# CPU.net
KiCad netlist of a schematic drawn in Altium Designer
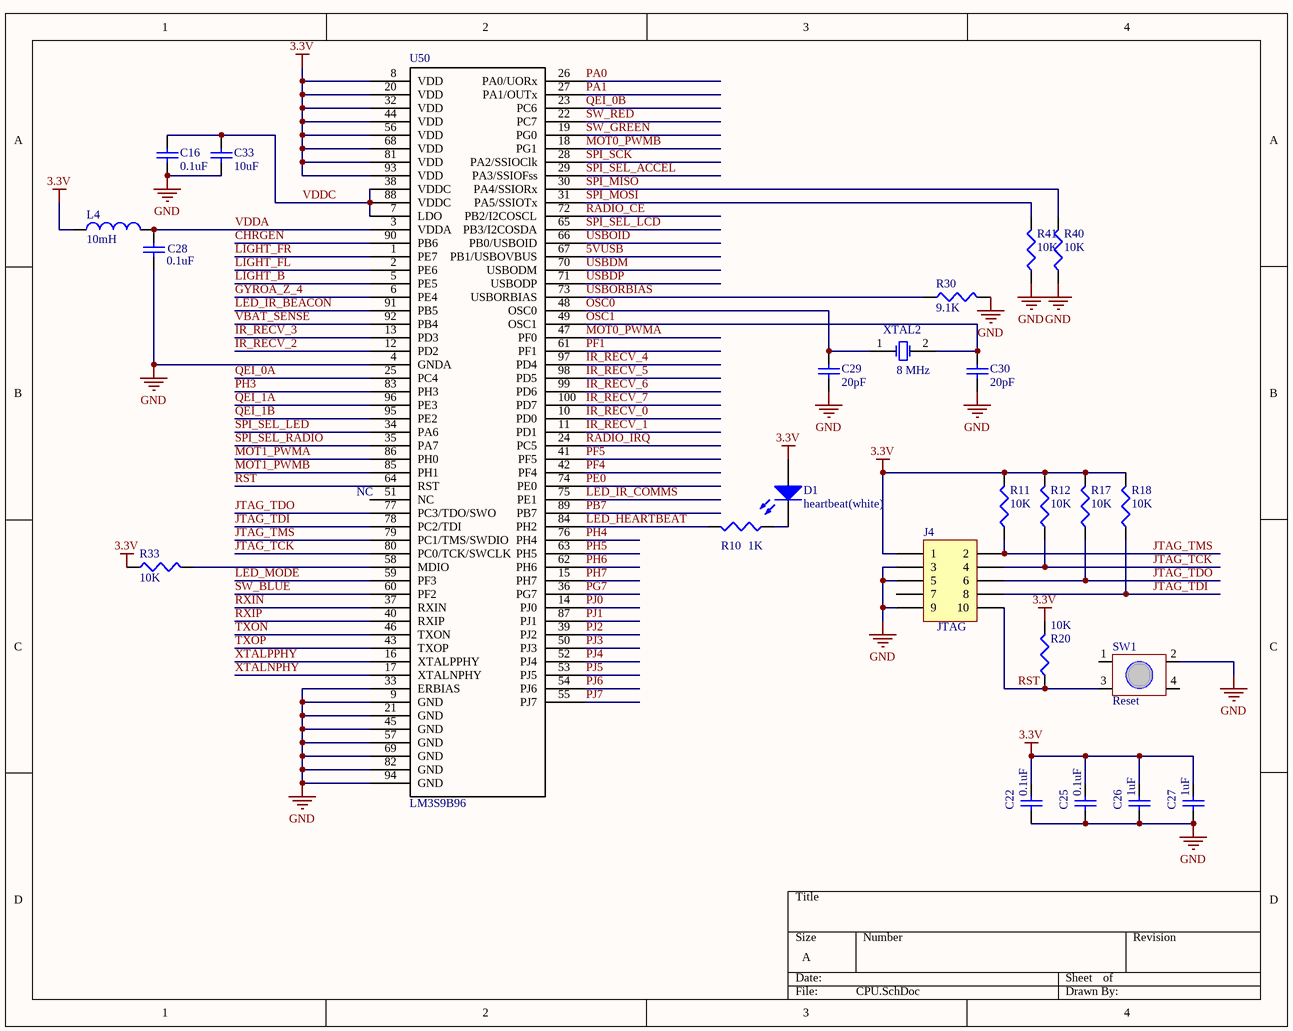
[diagram p0: CPU.SchDoc]

(export (version "E")
  (design (tool "Eeschema 10.0.6"))
  (components
    (comp (ref "C16")
      (value "0.1uF")
      (footprint "CAPC1005L")
      (description "Capacitor (Semiconductor SIM Model)")
      (fields (field (name "Comment") "Cap Semi") (field (name "PUBLISHER") "Altium Limited"))
      (libsource (lib "Miscellaneous Devices") (part "Cap Semi"))
    )
    (comp (ref "C22")
      (value "0.1uF")
      (footprint "CAPC1005L")
      (description "Capacitor (Semiconductor SIM Model)")
      (fields (field (name "Comment") "Cap Semi") (field (name "PUBLISHER") "Altium Limited"))
      (libsource (lib "Miscellaneous Devices") (part "Cap Semi"))
    )
    (comp (ref "C25")
      (value "0.1uF")
      (footprint "CAPC1005L")
      (description "Capacitor (Semiconductor SIM Model)")
      (fields (field (name "Comment") "Cap Semi") (field (name "PUBLISHER") "Altium Limited"))
      (libsource (lib "Miscellaneous Devices") (part "Cap Semi"))
    )
    (comp (ref "C26")
      (value "1uF")
      (footprint "CAPC1608L")
      (description "Capacitor (Semiconductor SIM Model)")
      (fields (field (name "Comment") "Cap Semi") (field (name "PUBLISHER") "Altium Limited"))
      (libsource (lib "Miscellaneous Devices") (part "Cap Semi"))
    )
    (comp (ref "C27")
      (value "1uF")
      (footprint "CAPC1608L")
      (description "Capacitor (Semiconductor SIM Model)")
      (fields (field (name "Comment") "Cap Semi") (field (name "PUBLISHER") "Altium Limited"))
      (libsource (lib "Miscellaneous Devices") (part "Cap Semi"))
    )
    (comp (ref "C28")
      (value "0.1uF")
      (footprint "CAPC1005L")
      (description "Capacitor (Semiconductor SIM Model)")
      (fields (field (name "Comment") "Cap Semi") (field (name "PUBLISHER") "Altium Limited"))
      (libsource (lib "Miscellaneous Devices") (part "Cap Semi"))
    )
    (comp (ref "C29")
      (value "20pF")
      (footprint "CAPC1005L")
      (description "Capacitor (Semiconductor SIM Model)")
      (fields (field (name "Comment") "Cap Semi") (field (name "PUBLISHER") "Altium Limited"))
      (libsource (lib "Miscellaneous Devices") (part "Cap Semi"))
    )
    (comp (ref "C30")
      (value "20pF")
      (footprint "CAPC1005L")
      (description "Capacitor (Semiconductor SIM Model)")
      (fields (field (name "Comment") "Cap Semi") (field (name "PUBLISHER") "Altium Limited"))
      (libsource (lib "Miscellaneous Devices") (part "Cap Semi"))
    )
    (comp (ref "C33")
      (value "10uF")
      (footprint "CAPC1005L")
      (description "Capacitor (Semiconductor SIM Model)")
      (fields (field (name "Comment") "Cap Semi") (field (name "PUBLISHER") "Altium Limited"))
      (libsource (lib "Miscellaneous Devices") (part "Cap Semi"))
    )
    (comp (ref "D1")
      (value "heartbeat(white)")
      (footprint "INDC2012L")
      (description "Typical RED, GREEN, YELLOW, AMBER GaAs LED")
      (fields (field (name "PUBLISHER") "Altium Limited"))
      (libsource (lib "Miscellaneous Devices") (part "LED2"))
    )
    (comp (ref "J4")
      (value "JTAG")
      (footprint "JTAG-10")
      (description "Header, 5-Pin, Dual row, Right Angle")
      (fields (field (name "PUBLISHER") "Altium Limited"))
      (libsource (lib "Miscellaneous Connectors") (part "Header 5X2H"))
    )
    (comp (ref "L4")
      (value "10mH")
      (footprint "INDC2012L")
      (description "Inductor")
      (fields (field (name "PUBLISHER") "Altium Limited"))
      (libsource (lib "Miscellaneous Devices") (part "Inductor"))
    )
    (comp (ref "R10")
      (value "1K")
      (footprint "RESC1608L")
      (description "Resistor")
      (fields (field (name "Comment") "Res3") (field (name "PUBLISHER") "Altium Limited"))
      (libsource (lib "Miscellaneous Devices") (part "Res3"))
    )
    (comp (ref "R11")
      (value "10K")
      (footprint "RESC1608L")
      (description "Resistor")
      (fields (field (name "Comment") "Res3") (field (name "PUBLISHER") "Altium Limited"))
      (libsource (lib "Miscellaneous Devices") (part "Res3"))
    )
    (comp (ref "R12")
      (value "10K")
      (footprint "RESC1608L")
      (description "Resistor")
      (fields (field (name "Comment") "Res3") (field (name "PUBLISHER") "Altium Limited"))
      (libsource (lib "Miscellaneous Devices") (part "Res3"))
    )
    (comp (ref "R17")
      (value "10K")
      (footprint "RESC1608L")
      (description "Resistor")
      (fields (field (name "Comment") "Res3") (field (name "PUBLISHER") "Altium Limited"))
      (libsource (lib "Miscellaneous Devices") (part "Res3"))
    )
    (comp (ref "R18")
      (value "10K")
      (footprint "RESC1608L")
      (description "Resistor")
      (fields (field (name "Comment") "Res3") (field (name "PUBLISHER") "Altium Limited"))
      (libsource (lib "Miscellaneous Devices") (part "Res3"))
    )
    (comp (ref "R20")
      (value "10K")
      (footprint "RESC1608L")
      (description "Resistor")
      (fields (field (name "Comment") "Res3") (field (name "PUBLISHER") "Altium Limited"))
      (libsource (lib "Miscellaneous Devices") (part "Res3"))
    )
    (comp (ref "R30")
      (value "9.1K")
      (footprint "RESC1608L")
      (description "Resistor")
      (fields (field (name "Comment") "Res3") (field (name "PUBLISHER") "Altium Limited"))
      (libsource (lib "Miscellaneous Devices") (part "Res3"))
    )
    (comp (ref "R33")
      (value "10K")
      (footprint "RESC1608L")
      (description "Resistor")
      (fields (field (name "Comment") "Res3") (field (name "PUBLISHER") "Altium Limited"))
      (libsource (lib "Miscellaneous Devices") (part "Res3"))
    )
    (comp (ref "R40")
      (value "10K")
      (footprint "RESC1608L")
      (description "Resistor")
      (fields (field (name "Comment") "Res3") (field (name "PUBLISHER") "Altium Limited"))
      (libsource (lib "Miscellaneous Devices") (part "Res3"))
    )
    (comp (ref "R41")
      (value "10K")
      (footprint "RESC1608L")
      (description "Resistor")
      (fields (field (name "Comment") "Res3") (field (name "PUBLISHER") "Altium Limited"))
      (libsource (lib "Miscellaneous Devices") (part "Res3"))
    )
    (comp (ref "SW1")
      (value "Reset")
      (footprint "SwitchTall-TL330")
      (libsource (lib "mrone") (part "Switch-TL330"))
    )
    (comp (ref "U50")
      (value "LM3S9B96")
      (footprint "LQFP-100")
      (libsource (lib "Schematic Components") (part "LM3S9B96"))
    )
    (comp (ref "XTAL2")
      (value "8 MHz")
      (footprint "RESC5025L")
      (description "Crystal Oscillator")
      (fields (field (name "PUBLISHER") "Altium Limited"))
      (libsource (lib "Miscellaneous Devices") (part "XTAL"))
    )
  )
  (nets
    (net (code "1") (name "/5VUSB") (class "Default")
      (node (ref "U50") (pin "67") (pinfunction "PB1/USBOVBUS_67") (pintype "passive"))
    )
    (net (code "2") (name "/CHRGEN") (class "Default")
      (node (ref "U50") (pin "90") (pinfunction "PB6_90") (pintype "passive"))
    )
    (net (code "3") (name "/GYROA_Z_4") (class "Default")
      (node (ref "U50") (pin "6") (pinfunction "PE4_6") (pintype "passive"))
    )
    (net (code "4") (name "/IR_RECV_0") (class "Default")
      (node (ref "U50") (pin "10") (pinfunction "PD0_10") (pintype "passive"))
    )
    (net (code "5") (name "/IR_RECV_1") (class "Default")
      (node (ref "U50") (pin "11") (pinfunction "PD1_11") (pintype "passive"))
    )
    (net (code "6") (name "/IR_RECV_2") (class "Default")
      (node (ref "U50") (pin "12") (pinfunction "PD2_12") (pintype "passive"))
    )
    (net (code "7") (name "/IR_RECV_3") (class "Default")
      (node (ref "U50") (pin "13") (pinfunction "PD3_13") (pintype "passive"))
    )
    (net (code "8") (name "/IR_RECV_4") (class "Default")
      (node (ref "U50") (pin "97") (pinfunction "PD4_97") (pintype "passive"))
    )
    (net (code "9") (name "/IR_RECV_5") (class "Default")
      (node (ref "U50") (pin "98") (pinfunction "PD5_98") (pintype "passive"))
    )
    (net (code "10") (name "/IR_RECV_6") (class "Default")
      (node (ref "U50") (pin "99") (pinfunction "PD6_99") (pintype "passive"))
    )
    (net (code "11") (name "/IR_RECV_7") (class "Default")
      (node (ref "U50") (pin "100") (pinfunction "PD7_100") (pintype "passive"))
    )
    (net (code "12") (name "/JTAG_TCK") (class "Default")
      (node (ref "J4") (pin "4") (pinfunction "4_4") (pintype "passive"))
      (node (ref "R12") (pin "1") (pinfunction "1_1") (pintype "passive"))
      (node (ref "U50") (pin "80") (pinfunction "PC0/TCK/SWCLK_80") (pintype "passive"))
    )
    (net (code "13") (name "/JTAG_TDI") (class "Default")
      (node (ref "J4") (pin "8") (pinfunction "8_8") (pintype "passive"))
      (node (ref "R18") (pin "1") (pinfunction "1_1") (pintype "passive"))
      (node (ref "U50") (pin "78") (pinfunction "PC2/TDI_78") (pintype "passive"))
    )
    (net (code "14") (name "/JTAG_TDO") (class "Default")
      (node (ref "J4") (pin "6") (pinfunction "6_6") (pintype "passive"))
      (node (ref "R17") (pin "1") (pinfunction "1_1") (pintype "passive"))
      (node (ref "U50") (pin "77") (pinfunction "PC3/TDO/SWO_77") (pintype "passive"))
    )
    (net (code "15") (name "/JTAG_TMS") (class "Default")
      (node (ref "J4") (pin "2") (pinfunction "2_2") (pintype "passive"))
      (node (ref "R11") (pin "1") (pinfunction "1_1") (pintype "passive"))
      (node (ref "U50") (pin "79") (pinfunction "PC1/TMS/SWDIO_79") (pintype "passive"))
    )
    (net (code "16") (name "/LED_HEARTBEAT") (class "Default")
      (node (ref "R10") (pin "2") (pinfunction "2_2") (pintype "passive"))
      (node (ref "U50") (pin "84") (pinfunction "PH2_84") (pintype "passive"))
    )
    (net (code "17") (name "/LED_IR_BEACON") (class "Default")
      (node (ref "U50") (pin "91") (pinfunction "PB5_91") (pintype "passive"))
    )
    (net (code "18") (name "/LED_IR_COMMS") (class "Default")
      (node (ref "U50") (pin "75") (pinfunction "PE1_75") (pintype "passive"))
    )
    (net (code "19") (name "/LED_MODE") (class "Default")
      (node (ref "U50") (pin "59") (pinfunction "PF3_59") (pintype "passive"))
    )
    (net (code "20") (name "/LIGHT_B") (class "Default")
      (node (ref "U50") (pin "5") (pinfunction "PE5_5") (pintype "passive"))
    )
    (net (code "21") (name "/LIGHT_FL") (class "Default")
      (node (ref "U50") (pin "2") (pinfunction "PE6_2") (pintype "passive"))
    )
    (net (code "22") (name "/LIGHT_FR") (class "Default")
      (node (ref "U50") (pin "1") (pinfunction "PE7_1") (pintype "passive"))
    )
    (net (code "23") (name "/MOT0_PWMA") (class "Default")
      (node (ref "U50") (pin "47") (pinfunction "PF0_47") (pintype "passive"))
    )
    (net (code "24") (name "/MOT0_PWMB") (class "Default")
      (node (ref "U50") (pin "18") (pinfunction "PG1_18") (pintype "passive"))
    )
    (net (code "25") (name "/MOT1_PWMA") (class "Default")
      (node (ref "U50") (pin "86") (pinfunction "PH0_86") (pintype "passive"))
    )
    (net (code "26") (name "/MOT1_PWMB") (class "Default")
      (node (ref "U50") (pin "85") (pinfunction "PH1_85") (pintype "passive"))
    )
    (net (code "27") (name "/OSC0") (class "Default")
      (node (ref "C29") (pin "2") (pinfunction "2_2") (pintype "passive"))
      (node (ref "U50") (pin "48") (pinfunction "OSC0_48") (pintype "passive"))
      (node (ref "XTAL2") (pin "1") (pinfunction "OSC1_1") (pintype "passive"))
    )
    (net (code "28") (name "/OSC1") (class "Default")
      (node (ref "C30") (pin "2") (pinfunction "2_2") (pintype "passive"))
      (node (ref "U50") (pin "49") (pinfunction "OSC1_49") (pintype "passive"))
      (node (ref "XTAL2") (pin "2") (pinfunction "OSC2_2") (pintype "passive"))
    )
    (net (code "29") (name "/PA0") (class "Default")
      (node (ref "U50") (pin "26") (pinfunction "PA0/UORx_26") (pintype "passive"))
    )
    (net (code "30") (name "/PA1") (class "Default")
      (node (ref "U50") (pin "27") (pinfunction "PA1/OUTx_27") (pintype "passive"))
    )
    (net (code "31") (name "/PB7") (class "Default")
      (node (ref "U50") (pin "89") (pinfunction "PB7_89") (pintype "passive"))
    )
    (net (code "32") (name "/PE0") (class "Default")
      (node (ref "U50") (pin "74") (pinfunction "PE0_74") (pintype "passive"))
    )
    (net (code "33") (name "/PF1") (class "Default")
      (node (ref "U50") (pin "61") (pinfunction "PF1_61") (pintype "passive"))
    )
    (net (code "34") (name "/PF4") (class "Default")
      (node (ref "U50") (pin "42") (pinfunction "PF4_42") (pintype "passive"))
    )
    (net (code "35") (name "/PF5") (class "Default")
      (node (ref "U50") (pin "41") (pinfunction "PF5_41") (pintype "passive"))
    )
    (net (code "36") (name "/PG7") (class "Default")
      (node (ref "U50") (pin "36") (pinfunction "PG7_36") (pintype "passive"))
    )
    (net (code "37") (name "/PH3") (class "Default")
      (node (ref "U50") (pin "83") (pinfunction "PH3_83") (pintype "passive"))
    )
    (net (code "38") (name "/PH4") (class "Default")
      (node (ref "U50") (pin "76") (pinfunction "PH4_76") (pintype "passive"))
    )
    (net (code "39") (name "/PH5") (class "Default")
      (node (ref "U50") (pin "63") (pinfunction "PH5_63") (pintype "passive"))
    )
    (net (code "40") (name "/PH6") (class "Default")
      (node (ref "U50") (pin "62") (pinfunction "PH6_62") (pintype "passive"))
    )
    (net (code "41") (name "/PH7") (class "Default")
      (node (ref "U50") (pin "15") (pinfunction "PH7_15") (pintype "passive"))
    )
    (net (code "42") (name "/PJ0") (class "Default")
      (node (ref "U50") (pin "14") (pinfunction "PJ0_14") (pintype "passive"))
    )
    (net (code "43") (name "/PJ1") (class "Default")
      (node (ref "U50") (pin "87") (pinfunction "PJ1_87") (pintype "passive"))
    )
    (net (code "44") (name "/PJ2") (class "Default")
      (node (ref "U50") (pin "39") (pinfunction "PJ2_39") (pintype "passive"))
    )
    (net (code "45") (name "/PJ3") (class "Default")
      (node (ref "U50") (pin "50") (pinfunction "PJ3_50") (pintype "passive"))
    )
    (net (code "46") (name "/PJ4") (class "Default")
      (node (ref "U50") (pin "52") (pinfunction "PJ4_52") (pintype "passive"))
    )
    (net (code "47") (name "/PJ5") (class "Default")
      (node (ref "U50") (pin "53") (pinfunction "PJ5_53") (pintype "passive"))
    )
    (net (code "48") (name "/PJ6") (class "Default")
      (node (ref "U50") (pin "54") (pinfunction "PJ6_54") (pintype "passive"))
    )
    (net (code "49") (name "/PJ7") (class "Default")
      (node (ref "U50") (pin "55") (pinfunction "PJ7_55") (pintype "passive"))
    )
    (net (code "50") (name "/QEI_0A") (class "Default")
      (node (ref "U50") (pin "25") (pinfunction "PC4_25") (pintype "passive"))
    )
    (net (code "51") (name "/QEI_0B") (class "Default")
      (node (ref "U50") (pin "23") (pinfunction "PC6_23") (pintype "passive"))
    )
    (net (code "52") (name "/QEI_1A") (class "Default")
      (node (ref "U50") (pin "96") (pinfunction "PE3_96") (pintype "passive"))
    )
    (net (code "53") (name "/QEI_1B") (class "Default")
      (node (ref "U50") (pin "95") (pinfunction "PE2_95") (pintype "passive"))
    )
    (net (code "54") (name "/RADIO_CE") (class "Default")
      (node (ref "U50") (pin "72") (pinfunction "PB2/I2COSCL_72") (pintype "passive"))
    )
    (net (code "55") (name "/RADIO_IRQ") (class "Default")
      (node (ref "U50") (pin "24") (pinfunction "PC5_24") (pintype "passive"))
    )
    (net (code "56") (name "/RST") (class "Default")
      (node (ref "J4") (pin "10") (pinfunction "10_10") (pintype "passive"))
      (node (ref "R20") (pin "1") (pinfunction "1_1") (pintype "passive"))
      (node (ref "SW1") (pin "3") (pinfunction "3_3") (pintype "passive"))
      (node (ref "U50") (pin "64") (pinfunction "RST_64") (pintype "passive"))
    )
    (net (code "57") (name "/RXIN") (class "Default")
      (node (ref "U50") (pin "37") (pinfunction "RXIN_37") (pintype "passive"))
    )
    (net (code "58") (name "/RXIP") (class "Default")
      (node (ref "U50") (pin "40") (pinfunction "RXIP_40") (pintype "passive"))
    )
    (net (code "59") (name "/SPI_MISO") (class "Default")
      (node (ref "R40") (pin "2") (pinfunction "2_2") (pintype "passive"))
      (node (ref "U50") (pin "30") (pinfunction "PA4/SSIORx_30") (pintype "passive"))
    )
    (net (code "60") (name "/SPI_MOSI") (class "Default")
      (node (ref "R41") (pin "2") (pinfunction "2_2") (pintype "passive"))
      (node (ref "U50") (pin "31") (pinfunction "PA5/SSIOTx_31") (pintype "passive"))
    )
    (net (code "61") (name "/SPI_SCK") (class "Default")
      (node (ref "U50") (pin "28") (pinfunction "PA2/SSIOClk_28") (pintype "passive"))
    )
    (net (code "62") (name "/SPI_SEL_ACCEL") (class "Default")
      (node (ref "U50") (pin "29") (pinfunction "PA3/SSIOFss_29") (pintype "passive"))
    )
    (net (code "63") (name "/SPI_SEL_LCD") (class "Default")
      (node (ref "U50") (pin "65") (pinfunction "PB3/I2COSDA_65") (pintype "passive"))
    )
    (net (code "64") (name "/SPI_SEL_LED") (class "Default")
      (node (ref "U50") (pin "34") (pinfunction "PA6_34") (pintype "passive"))
    )
    (net (code "65") (name "/SPI_SEL_RADIO") (class "Default")
      (node (ref "U50") (pin "35") (pinfunction "PA7_35") (pintype "passive"))
    )
    (net (code "66") (name "/SW_BLUE") (class "Default")
      (node (ref "U50") (pin "60") (pinfunction "PF2_60") (pintype "passive"))
    )
    (net (code "67") (name "/SW_GREEN") (class "Default")
      (node (ref "U50") (pin "19") (pinfunction "PG0_19") (pintype "passive"))
    )
    (net (code "68") (name "/SW_RED") (class "Default")
      (node (ref "U50") (pin "22") (pinfunction "PC7_22") (pintype "passive"))
    )
    (net (code "69") (name "/TXON") (class "Default")
      (node (ref "U50") (pin "46") (pinfunction "TXON_46") (pintype "passive"))
    )
    (net (code "70") (name "/TXOP") (class "Default")
      (node (ref "U50") (pin "43") (pinfunction "TXOP_43") (pintype "passive"))
    )
    (net (code "71") (name "/USBDM") (class "Default")
      (node (ref "U50") (pin "70") (pinfunction "USBODM_70") (pintype "passive"))
    )
    (net (code "72") (name "/USBDP") (class "Default")
      (node (ref "U50") (pin "71") (pinfunction "USBODP_71") (pintype "passive"))
    )
    (net (code "73") (name "/USBOID") (class "Default")
      (node (ref "U50") (pin "66") (pinfunction "PB0/USBOID_66") (pintype "passive"))
    )
    (net (code "74") (name "/USBORBIAS") (class "Default")
      (node (ref "R30") (pin "1") (pinfunction "1_1") (pintype "passive"))
      (node (ref "U50") (pin "73") (pinfunction "USBORBIAS_73") (pintype "passive"))
    )
    (net (code "75") (name "/VBAT_SENSE") (class "Default")
      (node (ref "U50") (pin "92") (pinfunction "PB4_92") (pintype "passive"))
    )
    (net (code "76") (name "/VDDA") (class "Default")
      (node (ref "C28") (pin "2") (pinfunction "2_2") (pintype "passive"))
      (node (ref "L4") (pin "2") (pinfunction "2_2") (pintype "passive"))
      (node (ref "U50") (pin "3") (pinfunction "VDDA_3") (pintype "passive"))
    )
    (net (code "77") (name "/VDDC") (class "Default")
      (node (ref "C16") (pin "2") (pinfunction "2_2") (pintype "passive"))
      (node (ref "C33") (pin "2") (pinfunction "2_2") (pintype "passive"))
      (node (ref "U50") (pin "38") (pinfunction "VDDC_38") (pintype "passive"))
      (node (ref "U50") (pin "7") (pinfunction "LDO_7") (pintype "passive"))
      (node (ref "U50") (pin "88") (pinfunction "VDDC_88") (pintype "passive"))
    )
    (net (code "78") (name "/XTALNPHY") (class "Default")
      (node (ref "U50") (pin "17") (pinfunction "XTALNPHY_17") (pintype "passive"))
    )
    (net (code "79") (name "/XTALPPHY") (class "Default")
      (node (ref "U50") (pin "16") (pinfunction "XTALPPHY_16") (pintype "passive"))
    )
    (net (code "80") (name "3.3V") (class "Default")
      (node (ref "C22") (pin "2") (pinfunction "2_2") (pintype "passive"))
      (node (ref "C25") (pin "2") (pinfunction "2_2") (pintype "passive"))
      (node (ref "C26") (pin "2") (pinfunction "2_2") (pintype "passive"))
      (node (ref "C27") (pin "2") (pinfunction "2_2") (pintype "passive"))
      (node (ref "D1") (pin "1") (pinfunction "A_1") (pintype "passive"))
      (node (ref "J4") (pin "1") (pinfunction "1_1") (pintype "passive"))
      (node (ref "L4") (pin "1") (pinfunction "1_1") (pintype "passive"))
      (node (ref "R11") (pin "2") (pinfunction "2_2") (pintype "passive"))
      (node (ref "R12") (pin "2") (pinfunction "2_2") (pintype "passive"))
      (node (ref "R17") (pin "2") (pinfunction "2_2") (pintype "passive"))
      (node (ref "R18") (pin "2") (pinfunction "2_2") (pintype "passive"))
      (node (ref "R20") (pin "2") (pinfunction "2_2") (pintype "passive"))
      (node (ref "R33") (pin "1") (pinfunction "1_1") (pintype "passive"))
      (node (ref "U50") (pin "20") (pinfunction "VDD_20") (pintype "passive"))
      (node (ref "U50") (pin "32") (pinfunction "VDD_32") (pintype "passive"))
      (node (ref "U50") (pin "44") (pinfunction "VDD_44") (pintype "passive"))
      (node (ref "U50") (pin "56") (pinfunction "VDD_56") (pintype "passive"))
      (node (ref "U50") (pin "68") (pinfunction "VDD_68") (pintype "passive"))
      (node (ref "U50") (pin "8") (pinfunction "VDD_8") (pintype "passive"))
      (node (ref "U50") (pin "81") (pinfunction "VDD_81") (pintype "passive"))
      (node (ref "U50") (pin "93") (pinfunction "VDD_93") (pintype "passive"))
    )
    (net (code "81") (name "GND") (class "Default")
      (node (ref "C16") (pin "1") (pinfunction "1_1") (pintype "passive"))
      (node (ref "C22") (pin "1") (pinfunction "1_1") (pintype "passive"))
      (node (ref "C25") (pin "1") (pinfunction "1_1") (pintype "passive"))
      (node (ref "C26") (pin "1") (pinfunction "1_1") (pintype "passive"))
      (node (ref "C27") (pin "1") (pinfunction "1_1") (pintype "passive"))
      (node (ref "C28") (pin "1") (pinfunction "1_1") (pintype "passive"))
      (node (ref "C29") (pin "1") (pinfunction "1_1") (pintype "passive"))
      (node (ref "C30") (pin "1") (pinfunction "1_1") (pintype "passive"))
      (node (ref "C33") (pin "1") (pinfunction "1_1") (pintype "passive"))
      (node (ref "J4") (pin "3") (pinfunction "3_3") (pintype "passive"))
      (node (ref "J4") (pin "5") (pinfunction "5_5") (pintype "passive"))
      (node (ref "J4") (pin "9") (pinfunction "9_9") (pintype "passive"))
      (node (ref "R30") (pin "2") (pinfunction "2_2") (pintype "passive"))
      (node (ref "R40") (pin "1") (pinfunction "1_1") (pintype "passive"))
      (node (ref "R41") (pin "1") (pinfunction "1_1") (pintype "passive"))
      (node (ref "SW1") (pin "2") (pinfunction "2_2") (pintype "passive"))
      (node (ref "U50") (pin "21") (pinfunction "GND_21") (pintype "passive"))
      (node (ref "U50") (pin "33") (pinfunction "ERBIAS_33") (pintype "passive"))
      (node (ref "U50") (pin "4") (pinfunction "GNDA_4") (pintype "passive"))
      (node (ref "U50") (pin "45") (pinfunction "GND_45") (pintype "passive"))
      (node (ref "U50") (pin "57") (pinfunction "GND_57") (pintype "passive"))
      (node (ref "U50") (pin "69") (pinfunction "GND_69") (pintype "passive"))
      (node (ref "U50") (pin "82") (pinfunction "GND_82") (pintype "passive"))
      (node (ref "U50") (pin "9") (pinfunction "GND_9") (pintype "passive"))
      (node (ref "U50") (pin "94") (pinfunction "GND_94") (pintype "passive"))
    )
    (net (code "82") (name "Net-(D1-K)") (class "Default")
      (node (ref "D1") (pin "2") (pinfunction "K_2") (pintype "passive"))
      (node (ref "R10") (pin "1") (pinfunction "1_1") (pintype "passive"))
    )
    (net (code "83") (name "Net-(U50-MDIO)") (class "Default")
      (node (ref "R33") (pin "2") (pinfunction "2_2") (pintype "passive"))
      (node (ref "U50") (pin "58") (pinfunction "MDIO_58") (pintype "passive"))
    )
    (net (code "84") (name "unconnected-(J4-Pad7)") (class "Default")
      (node (ref "J4") (pin "7") (pinfunction "7_7") (pintype "passive"))
    )
    (net (code "85") (name "unconnected-(SW1-Pad1)") (class "Default")
      (node (ref "SW1") (pin "1") (pinfunction "1_1") (pintype "passive"))
    )
    (net (code "86") (name "unconnected-(SW1-Pad4)") (class "Default")
      (node (ref "SW1") (pin "4") (pinfunction "4_4") (pintype "passive"))
    )
    (net (code "87") (name "unconnected-(U50-NC-Pad51)") (class "Default")
      (node (ref "U50") (pin "51") (pinfunction "NC_51") (pintype "passive"))
    )
  )
)
